# 03_-_28PINS_SCHEMATIC.net
KiCad netlist of a schematic drawn in Altium Designer
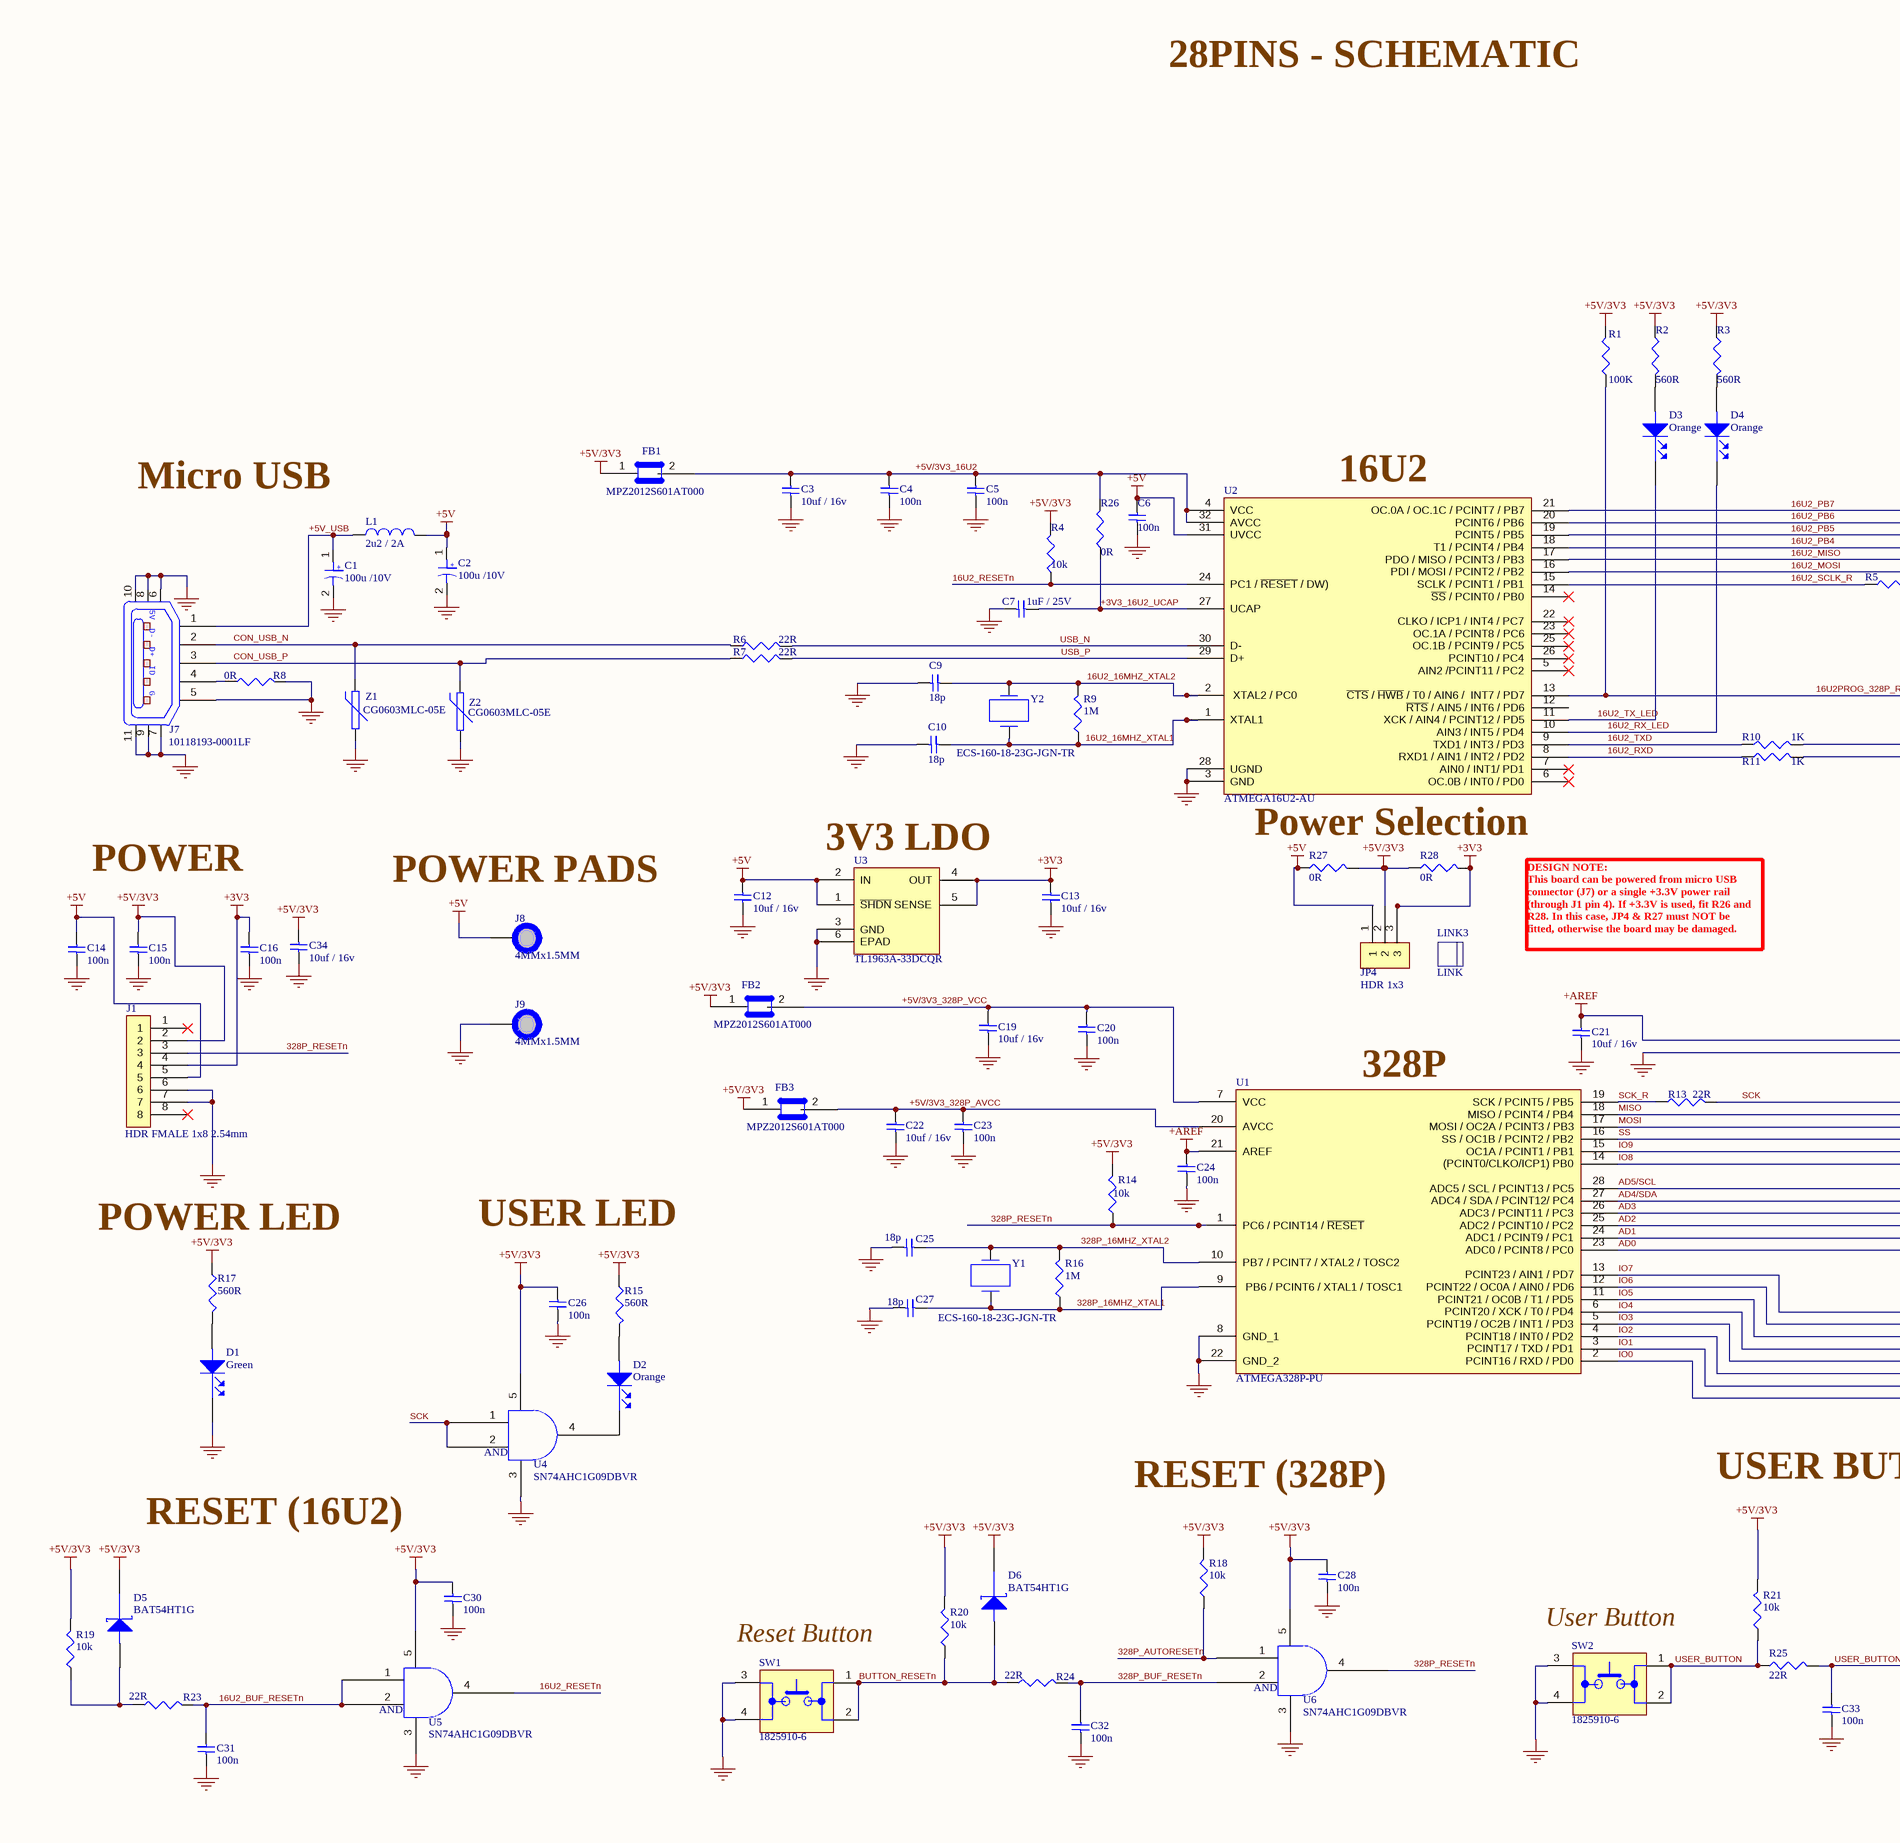
[diagram p0: [03] - 28PINS SCHEMATIC.SchDoc, left]
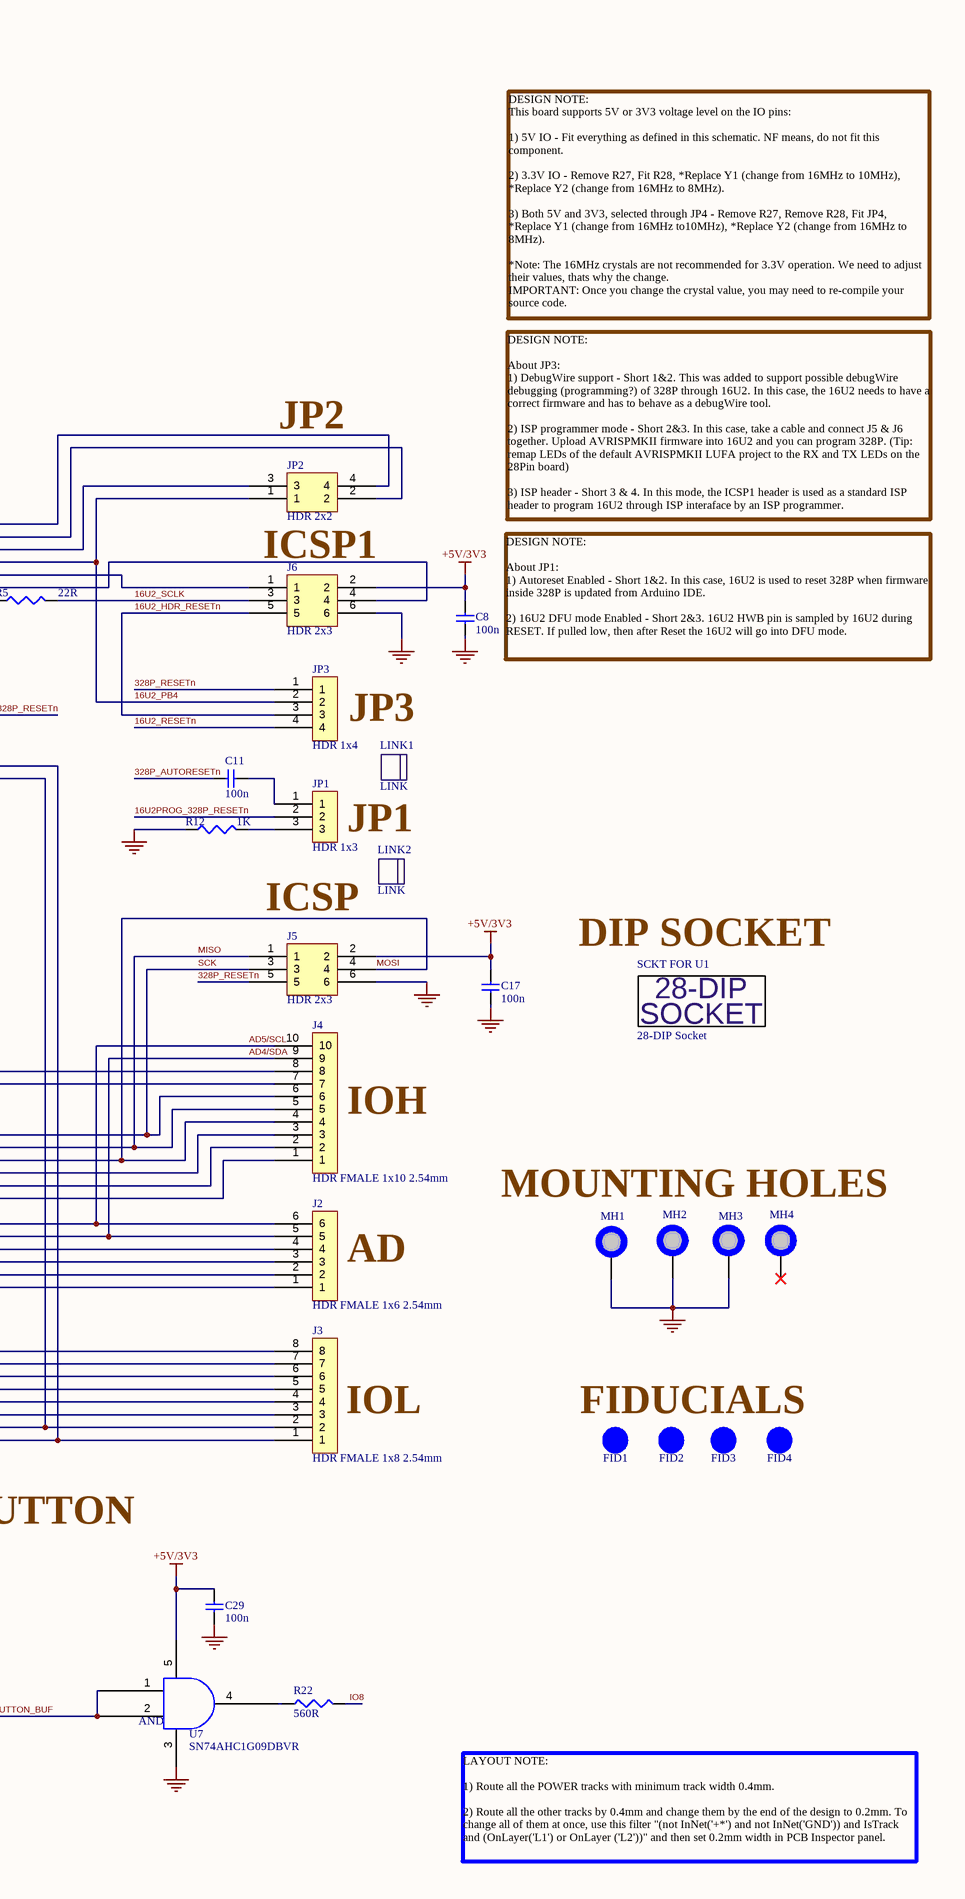
[diagram p1: [03] - 28PINS SCHEMATIC.SchDoc, right]

(export (version "E")
  (design (tool "Eeschema 10.0.6"))
  (components
    (comp (ref "C1")
      (value "100u /10V")
      (footprint "C_ALU_SIZE")
      (fields
        (field (name "MANUFACTURER") "Panasonic")
        (field (name "MANUFACTURER PART NUMBER") "EEE-1AA101WR")
      )
      (libsource (lib "28pins_project") (part "EEE-1AA101WR"))
    )
    (comp (ref "C2")
      (value "100u /10V")
      (footprint "C_ALU_SIZE")
      (fields
        (field (name "MANUFACTURER") "Panasonic")
        (field (name "MANUFACTURER PART NUMBER") "EEE-1AA101WR")
      )
      (libsource (lib "28pins_project") (part "EEE-1AA101WR"))
    )
    (comp (ref "C3")
      (value "10uf / 16v")
      (footprint "C0805")
      (fields
        (field (name "MANUFACTURER") "TDK")
        (field (name "MANUFACTURER PART NUMBER") "C2012X5R1C106M125AC")
      )
      (libsource (lib "28pins_project") (part "C2012X5R1C106M125AC"))
    )
    (comp (ref "C4")
      (value "100n")
      (footprint "C0805")
      (fields
        (field (name "MANUFACTURER") "TDK")
        (field (name "MANUFACTURER PART NUMBER") "C2012X7R1H104K085AA")
      )
      (libsource (lib "28pins_project") (part "C2012X7R1H104K085AA"))
    )
    (comp (ref "C5")
      (value "100n")
      (footprint "C0805")
      (fields
        (field (name "MANUFACTURER") "TDK")
        (field (name "MANUFACTURER PART NUMBER") "C2012X7R1H104K085AA")
      )
      (libsource (lib "28pins_project") (part "C2012X7R1H104K085AA"))
    )
    (comp (ref "C6")
      (value "100n")
      (footprint "C0805")
      (fields
        (field (name "MANUFACTURER") "TDK")
        (field (name "MANUFACTURER PART NUMBER") "C2012X7R1H104K085AA")
      )
      (libsource (lib "28pins_project") (part "C2012X7R1H104K085AA"))
    )
    (comp (ref "C7")
      (value "1uF / 25V")
      (footprint "C0805")
      (fields
        (field (name "MANUFACTURER") "TDK")
        (field (name "MANUFACTURER PART NUMBER") "C2012X5R1E105K125AA")
      )
      (libsource (lib "28pins_project") (part "C2012X5R1E105K125AA"))
    )
    (comp (ref "C8")
      (value "100n")
      (footprint "C0805")
      (fields
        (field (name "MANUFACTURER") "TDK")
        (field (name "MANUFACTURER PART NUMBER") "C2012X7R1H104K085AA")
      )
      (libsource (lib "28pins_project") (part "C2012X7R1H104K085AA"))
    )
    (comp (ref "C9")
      (value "18p")
      (footprint "C0805")
      (fields
        (field (name "MANUFACTURER") "KEMET")
        (field (name "MANUFACTURER PART NUMBER") "C0805C180J5GACTU")
      )
      (libsource (lib "28pins_project") (part "C0805C180J5GACTU"))
    )
    (comp (ref "C10")
      (value "18p")
      (footprint "C0805")
      (fields
        (field (name "MANUFACTURER") "KEMET")
        (field (name "MANUFACTURER PART NUMBER") "C0805C180J5GACTU")
      )
      (libsource (lib "28pins_project") (part "C0805C180J5GACTU"))
    )
    (comp (ref "C11")
      (value "100n")
      (footprint "C0805")
      (fields
        (field (name "MANUFACTURER") "TDK")
        (field (name "MANUFACTURER PART NUMBER") "C2012X7R1H104K085AA")
      )
      (libsource (lib "28pins_project") (part "C2012X7R1H104K085AA"))
    )
    (comp (ref "C12")
      (value "10uf / 16v")
      (footprint "C0805")
      (fields
        (field (name "MANUFACTURER") "TDK")
        (field (name "MANUFACTURER PART NUMBER") "C2012X5R1C106M125AC")
      )
      (libsource (lib "28pins_project") (part "C2012X5R1C106M125AC"))
    )
    (comp (ref "C13")
      (value "10uf / 16v")
      (footprint "C0805")
      (fields
        (field (name "MANUFACTURER") "TDK")
        (field (name "MANUFACTURER PART NUMBER") "C2012X5R1C106M125AC")
      )
      (libsource (lib "28pins_project") (part "C2012X5R1C106M125AC"))
    )
    (comp (ref "C14")
      (value "100n")
      (footprint "C0805")
      (fields
        (field (name "MANUFACTURER") "TDK")
        (field (name "MANUFACTURER PART NUMBER") "C2012X7R1H104K085AA")
      )
      (libsource (lib "28pins_project") (part "C2012X7R1H104K085AA"))
    )
    (comp (ref "C15")
      (value "100n")
      (footprint "C0805")
      (fields
        (field (name "MANUFACTURER") "TDK")
        (field (name "MANUFACTURER PART NUMBER") "C2012X7R1H104K085AA")
      )
      (libsource (lib "28pins_project") (part "C2012X7R1H104K085AA"))
    )
    (comp (ref "C16")
      (value "100n")
      (footprint "C0805")
      (fields
        (field (name "MANUFACTURER") "TDK")
        (field (name "MANUFACTURER PART NUMBER") "C2012X7R1H104K085AA")
      )
      (libsource (lib "28pins_project") (part "C2012X7R1H104K085AA"))
    )
    (comp (ref "C17")
      (value "100n")
      (footprint "C0805")
      (fields
        (field (name "MANUFACTURER") "TDK")
        (field (name "MANUFACTURER PART NUMBER") "C2012X7R1H104K085AA")
      )
      (libsource (lib "28pins_project") (part "C2012X7R1H104K085AA"))
    )
    (comp (ref "C19")
      (value "10uf / 16v")
      (footprint "C0805")
      (fields
        (field (name "MANUFACTURER") "TDK")
        (field (name "MANUFACTURER PART NUMBER") "C2012X5R1C106M125AC")
      )
      (libsource (lib "28pins_project") (part "C2012X5R1C106M125AC"))
    )
    (comp (ref "C20")
      (value "100n")
      (footprint "C0805")
      (fields
        (field (name "MANUFACTURER") "TDK")
        (field (name "MANUFACTURER PART NUMBER") "C2012X7R1H104K085AA")
      )
      (libsource (lib "28pins_project") (part "C2012X7R1H104K085AA"))
    )
    (comp (ref "C21")
      (value "10uf / 16v")
      (footprint "C0805")
      (fields
        (field (name "MANUFACTURER") "TDK")
        (field (name "MANUFACTURER PART NUMBER") "C2012X5R1C106M125AC")
      )
      (libsource (lib "28pins_project") (part "C2012X5R1C106M125AC"))
    )
    (comp (ref "C22")
      (value "10uf / 16v")
      (footprint "C0805")
      (fields
        (field (name "MANUFACTURER") "TDK")
        (field (name "MANUFACTURER PART NUMBER") "C2012X5R1C106M125AC")
      )
      (libsource (lib "28pins_project") (part "C2012X5R1C106M125AC"))
    )
    (comp (ref "C23")
      (value "100n")
      (footprint "C0805")
      (fields
        (field (name "MANUFACTURER") "TDK")
        (field (name "MANUFACTURER PART NUMBER") "C2012X7R1H104K085AA")
      )
      (libsource (lib "28pins_project") (part "C2012X7R1H104K085AA"))
    )
    (comp (ref "C24")
      (value "100n")
      (footprint "C0805")
      (fields
        (field (name "MANUFACTURER") "TDK")
        (field (name "MANUFACTURER PART NUMBER") "C2012X7R1H104K085AA")
      )
      (libsource (lib "28pins_project") (part "C2012X7R1H104K085AA"))
    )
    (comp (ref "C25")
      (value "18p")
      (footprint "C0805")
      (fields
        (field (name "MANUFACTURER") "KEMET")
        (field (name "MANUFACTURER PART NUMBER") "C0805C180J5GACTU")
      )
      (libsource (lib "28pins_project") (part "C0805C180J5GACTU"))
    )
    (comp (ref "C26")
      (value "100n")
      (footprint "C0805")
      (fields
        (field (name "MANUFACTURER") "TDK")
        (field (name "MANUFACTURER PART NUMBER") "C2012X7R1H104K085AA")
      )
      (libsource (lib "28pins_project") (part "C2012X7R1H104K085AA"))
    )
    (comp (ref "C27")
      (value "18p")
      (footprint "C0805")
      (fields
        (field (name "MANUFACTURER") "KEMET")
        (field (name "MANUFACTURER PART NUMBER") "C0805C180J5GACTU")
      )
      (libsource (lib "28pins_project") (part "C0805C180J5GACTU"))
    )
    (comp (ref "C28")
      (value "100n")
      (footprint "C0805")
      (fields
        (field (name "MANUFACTURER") "TDK")
        (field (name "MANUFACTURER PART NUMBER") "C2012X7R1H104K085AA")
      )
      (libsource (lib "28pins_project") (part "C2012X7R1H104K085AA"))
    )
    (comp (ref "C29")
      (value "100n")
      (footprint "C0805")
      (fields
        (field (name "MANUFACTURER") "TDK")
        (field (name "MANUFACTURER PART NUMBER") "C2012X7R1H104K085AA")
      )
      (libsource (lib "28pins_project") (part "C2012X7R1H104K085AA"))
    )
    (comp (ref "C30")
      (value "100n")
      (footprint "C0805")
      (fields
        (field (name "MANUFACTURER") "TDK")
        (field (name "MANUFACTURER PART NUMBER") "C2012X7R1H104K085AA")
      )
      (libsource (lib "28pins_project") (part "C2012X7R1H104K085AA"))
    )
    (comp (ref "C31")
      (value "100n")
      (footprint "C0805")
      (fields
        (field (name "MANUFACTURER") "TDK")
        (field (name "MANUFACTURER PART NUMBER") "C2012X7R1H104K085AA")
      )
      (libsource (lib "28pins_project") (part "C2012X7R1H104K085AA"))
    )
    (comp (ref "C32")
      (value "100n")
      (footprint "C0805")
      (fields
        (field (name "MANUFACTURER") "TDK")
        (field (name "MANUFACTURER PART NUMBER") "C2012X7R1H104K085AA")
      )
      (libsource (lib "28pins_project") (part "C2012X7R1H104K085AA"))
    )
    (comp (ref "C33")
      (value "100n")
      (footprint "C0805")
      (fields
        (field (name "MANUFACTURER") "TDK")
        (field (name "MANUFACTURER PART NUMBER") "C2012X7R1H104K085AA")
      )
      (libsource (lib "28pins_project") (part "C2012X7R1H104K085AA"))
    )
    (comp (ref "C34")
      (value "10uf / 16v")
      (footprint "C0805")
      (fields
        (field (name "MANUFACTURER") "TDK")
        (field (name "MANUFACTURER PART NUMBER") "C2012X5R1C106M125AC")
      )
      (libsource (lib "28pins_project") (part "C2012X5R1C106M125AC"))
    )
    (comp (ref "D1")
      (value "Green")
      (footprint "LED_0603")
      (description "Single Color LED, Green, Colorless Diffused, 1.3mm")
      (fields
        (field (name "MANUFACTURER") "Osram Opto")
        (field (name "MANUFACTURER PART NUMBER") "LGL29K-G2J1-24-Z")
      )
      (libsource (lib "28pins_project") (part "LGL29K-G2J1-24-Z"))
    )
    (comp (ref "D2")
      (value "Orange")
      (footprint "LED_0603")
      (description "Single Color LED, Orange, Colorless Diffused, 1.3mm")
      (fields
        (field (name "MANUFACTURER") "Osram Opto")
        (field (name "MANUFACTURER PART NUMBER") "LOL29K-J2L1-24-Z")
      )
      (libsource (lib "28pins_project") (part "LOL29K-J2L1-24-Z"))
    )
    (comp (ref "D3")
      (value "Orange")
      (footprint "LED_0603")
      (description "Single Color LED, Orange, Colorless Diffused, 1.3mm")
      (fields
        (field (name "MANUFACTURER") "Osram Opto")
        (field (name "MANUFACTURER PART NUMBER") "LOL29K-J2L1-24-Z")
      )
      (libsource (lib "28pins_project") (part "LOL29K-J2L1-24-Z"))
    )
    (comp (ref "D4")
      (value "Orange")
      (footprint "LED_0603")
      (description "Single Color LED, Orange, Colorless Diffused, 1.3mm")
      (fields
        (field (name "MANUFACTURER") "Osram Opto")
        (field (name "MANUFACTURER PART NUMBER") "LOL29K-J2L1-24-Z")
      )
      (libsource (lib "28pins_project") (part "LOL29K-J2L1-24-Z"))
    )
    (comp (ref "D5")
      (value "BAT54HT1G")
      (footprint "SOD323")
      (description "Rectifier Diode, 1 Phase, 1 Element, 0.2A, 30V V(RRM), Silicon")
      (fields (field (name "MANUFACTURER") "ON Semiconductor / Fairchild"))
      (libsource (lib "28pins_project") (part "BAT54HT1G"))
    )
    (comp (ref "D6")
      (value "BAT54HT1G")
      (footprint "SOD323")
      (description "Rectifier Diode, 1 Phase, 1 Element, 0.2A, 30V V(RRM), Silicon")
      (fields (field (name "MANUFACTURER") "ON Semiconductor / Fairchild"))
      (libsource (lib "28pins_project") (part "BAT54HT1G"))
    )
    (comp (ref "FB1")
      (value "MPZ2012S601AT000")
      (footprint "C0805")
      (description "Ferrite Chip, 1 Function(s), 2A")
      (fields (field (name "MANUFACTURER") "TDK"))
      (libsource (lib "28pins_project") (part "MPZ2012S601AT000"))
    )
    (comp (ref "FB2")
      (value "MPZ2012S601AT000")
      (footprint "C0805")
      (description "Ferrite Chip, 1 Function(s), 2A")
      (fields (field (name "MANUFACTURER") "TDK"))
      (libsource (lib "28pins_project") (part "MPZ2012S601AT000"))
    )
    (comp (ref "FB3")
      (value "MPZ2012S601AT000")
      (footprint "C0805")
      (description "Ferrite Chip, 1 Function(s), 2A")
      (fields (field (name "MANUFACTURER") "TDK"))
      (libsource (lib "28pins_project") (part "MPZ2012S601AT000"))
    )
    (comp (ref "FID1")
      (value "FID_1MMC")
      (footprint "FID_40x120D")
      (description "Fiducial 40mil Diameter, 120mil Mask")
      (libsource (lib "28pins_project") (part "FID_1MMC"))
    )
    (comp (ref "FID2")
      (value "FID_1MMC")
      (footprint "FID_40x120D")
      (description "Fiducial 40mil Diameter, 120mil Mask")
      (libsource (lib "28pins_project") (part "FID_1MMC"))
    )
    (comp (ref "FID3")
      (value "FID_1MMC")
      (footprint "FID_40x120D")
      (description "Fiducial 40mil Diameter, 120mil Mask")
      (libsource (lib "28pins_project") (part "FID_1MMC"))
    )
    (comp (ref "FID4")
      (value "FID_1MMC")
      (footprint "FID_40x120D")
      (description "Fiducial 40mil Diameter, 120mil Mask")
      (libsource (lib "28pins_project") (part "FID_1MMC"))
    )
    (comp (ref "J1")
      (value "HDR FMALE 1x8 2.54mm")
      (footprint "Hdr_Female_1x8_2.54mm")
      (fields (field (name "MANUFACTURER") "Harwin") (field (name "MANUFACTURER PART NUMBER") "M20-7820842"))
      (libsource (lib "") (part "M20-7820842_1"))
    )
    (comp (ref "J2")
      (value "HDR FMALE 1x6 2.54mm")
      (footprint "Hdr_Female_1x6_2.5mm")
      (fields (field (name "MANUFACTURER") "Harwin") (field (name "MANUFACTURER PART NUMBER") "M20-7820646"))
      (libsource (lib "28pins_project") (part "M20-7820646"))
    )
    (comp (ref "J3")
      (value "HDR FMALE 1x8 2.54mm")
      (footprint "Hdr_Female_1x8_2.54mm")
      (fields (field (name "MANUFACTURER") "Harwin") (field (name "MANUFACTURER PART NUMBER") "M20-7820842"))
      (libsource (lib "28pins_project") (part "M20-7820842"))
    )
    (comp (ref "J4")
      (value "HDR FMALE 1x10 2.54mm")
      (footprint "Hdr_Female_1x10_2.54mm")
      (fields (field (name "MANUFACTURER") "Harwin") (field (name "MANUFACTURER PART NUMBER") "M20-7821046"))
      (libsource (lib "28pins_project") (part "M20-7821046"))
    )
    (comp (ref "J5")
      (value "HDR 2x3")
      (footprint "HDR_2x3_2.54mm")
      (description "Conn Unshrouded Header HDR 6 POS 2.54mm Solder ST Top Entry Thru-Hole BergStik® Bulk")
      (fields (field (name "MANUFACTURER") "ICC") (field (name "MANUFACTURER PART NUMBER") "67997-106HLF"))
      (libsource (lib "28pins_project") (part "67997-106HLF"))
    )
    (comp (ref "J6")
      (value "HDR 2x3")
      (footprint "HDR_2x3_2.54mm")
      (description "Conn Unshrouded Header HDR 6 POS 2.54mm Solder ST Top Entry Thru-Hole BergStik® Bulk")
      (fields (field (name "MANUFACTURER") "ICC") (field (name "MANUFACTURER PART NUMBER") "67997-106HLF"))
      (libsource (lib "28pins_project") (part "67997-106HLF"))
    )
    (comp (ref "J7")
      (value "10118193-0001LF")
      (footprint "10118193")
      (description "USB Connector, 5 Contact(s), Female, Right Angle, Surface Mount Terminal, Locking, Receptacle")
      (fields (field (name "MANUFACTURER") "Amphenol Communications Solutions"))
      (libsource (lib "28pins_project") (part "10118193-0001LF"))
    )
    (comp (ref "J8")
      (value "4MMx1.5MM")
      (footprint "PAD_WITH_HOLE_4MMx1.5MM")
      (description "PAD_WITH_HOLE_4MMx1.5MM")
      (libsource (lib "28pins_project") (part "PAD_WITH_HOLE_4MMx1.5MM"))
    )
    (comp (ref "J9")
      (value "4MMx1.5MM")
      (footprint "PAD_WITH_HOLE_4MMx1.5MM")
      (description "PAD_WITH_HOLE_4MMx1.5MM")
      (libsource (lib "28pins_project") (part "PAD_WITH_HOLE_4MMx1.5MM"))
    )
    (comp (ref "JP1")
      (value "HDR 1x3")
      (footprint "Hdr_Female_1x3_2.54mm")
      (description "Conn Unshrouded Header HDR 3 POS 2.54mm Solder ST Top Entry Thru-Hole BergStik® Automotive Bulk")
      (fields (field (name "MANUFACTURER") "ICC") (field (name "MANUFACTURER PART NUMBER") "68000-103HLF"))
      (libsource (lib "28pins_project") (part "68000-103HLF"))
    )
    (comp (ref "JP2")
      (value "HDR 2x2")
      (footprint "HDR_2x2_2.54mm")
      (description "Conn Unshrouded Header HDR 4 POS 2.54mm Solder ST Top Entry Thru-Hole BergStik® Bulk")
      (fields
        (field (name "MANUFACTURER") "Amphenol ICC / FCI")
        (field (name "MANUFACTURER PART NUMBER") "68602-204HLF")
      )
      (libsource (lib "28pins_project") (part "68602-204HLF"))
    )
    (comp (ref "JP3")
      (value "HDR 1x4")
      (footprint "Hdr_Female_1x4_2.5mm")
      (description "Conn Unshrouded Header HDR 4 POS 2.54mm Solder ST Thru-Hole Bag")
      (fields
        (field (name "MANUFACTURER") "Amphenol ICC / FCI")
        (field (name "MANUFACTURER PART NUMBER") "68001-204HLF")
      )
      (libsource (lib "28pins_project") (part "68001-204HLF"))
    )
    (comp (ref "JP4")
      (value "HDR 1x3")
      (footprint "Hdr_Female_1x3_2.54mm")
      (description "Conn Unshrouded Header HDR 3 POS 2.54mm Solder ST Top Entry Thru-Hole BergStik® Automotive Bulk")
      (fields (field (name "MANUFACTURER") "ICC") (field (name "MANUFACTURER PART NUMBER") "68000-103HLF"))
      (libsource (lib "") (part "68000-103HLF_1"))
    )
    (comp (ref "L1")
      (value "2u2 / 2A")
      (footprint "C1210_IND")
      (description "General Purpose Inductor, 2.2uH, 20%, 1 Element, Ferrite-Core, SMD, 1210")
      (fields
        (field (name "MANUFACTURER") "KEMET")
        (field (name "MANUFACTURER PART NUMBER") "L1210R2R2MDWIT")
      )
      (libsource (lib "28pins_project") (part "L1210R2R2MDWIT"))
    )
    (comp (ref "LINK1")
      (value "LINK")
      (description "Shunts/Jumper Connector")
      (fields
        (field (name "MANUFACTURER") "Sullins")
        (field (name "MANUFACTURER PART NUMBER") "QPC02SXGN-RC")
      )
      (libsource (lib "28pins_project") (part "QPC02SXGN-RC"))
    )
    (comp (ref "LINK2")
      (value "LINK")
      (description "Shunts/Jumper Connector")
      (fields
        (field (name "MANUFACTURER") "Sullins")
        (field (name "MANUFACTURER PART NUMBER") "QPC02SXGN-RC")
      )
      (libsource (lib "28pins_project") (part "QPC02SXGN-RC"))
    )
    (comp (ref "LINK3")
      (value "LINK")
      (description "Shunts/Jumper Connector")
      (fields
        (field (name "MANUFACTURER") "Sullins")
        (field (name "MANUFACTURER PART NUMBER") "QPC02SXGN-RC")
      )
      (libsource (lib "28pins_project") (part "QPC02SXGN-RC"))
    )
    (comp (ref "MH1")
      (value "MH_7.4MMC_3.2MMD")
      (footprint "MH_7.4MMC_3.2MMD")
      (description "Mounting Hole 7.4mm Diameter, 3.2mm Drill")
      (libsource (lib "28pins_project") (part "MH_7.4MMC_3.2MMD"))
    )
    (comp (ref "MH2")
      (value "MH_7.4MMC_3.2MMD")
      (footprint "MH_7.4MMC_3.2MMD")
      (description "Mounting Hole 7.4mm Diameter, 3.2mm Drill")
      (libsource (lib "28pins_project") (part "MH_7.4MMC_3.2MMD"))
    )
    (comp (ref "MH3")
      (value "MH_7.4MMC_3.2MMD")
      (footprint "MH_7.4MMC_3.2MMD")
      (description "Mounting Hole 7.4mm Diameter, 3.2mm Drill")
      (libsource (lib "28pins_project") (part "MH_7.4MMC_3.2MMD"))
    )
    (comp (ref "MH4")
      (value "MH_7.4MMNC_3.2MMD")
      (footprint "MH_7.4MMC_3.2MMD_NON_COPPER_NPTH")
      (description "Hole 7.4MM Diameter (Non Copper), 3.2MM Drill NPTH")
      (libsource (lib "28pins_project") (part "MH_7.4MMNC_3.2MMD"))
    )
    (comp (ref "R1")
      (value "100K")
      (footprint "R0805")
      (fields
        (field (name "MANUFACTURER") "Yageo")
        (field (name "MANUFACTURER PART NUMBER") "RC0805FR-0710KL")
        (field (name "TOLERANCE") "1%")
      )
      (libsource (lib "28pins_project") (part "RC0805FR-0710KL (3)"))
    )
    (comp (ref "R2")
      (value "560R")
      (footprint "R0805")
      (fields
        (field (name "MANUFACTURER") "Yageo")
        (field (name "MANUFACTURER PART NUMBER") "RC0805FR-075R6L")
        (field (name "TOLERANCE") "1%")
      )
      (libsource (lib "28pins_project") (part "RC0805FR-075R6L"))
    )
    (comp (ref "R3")
      (value "560R")
      (footprint "R0805")
      (fields
        (field (name "MANUFACTURER") "Yageo")
        (field (name "MANUFACTURER PART NUMBER") "RC0805FR-075R6L")
        (field (name "TOLERANCE") "1%")
      )
      (libsource (lib "28pins_project") (part "RC0805FR-075R6L"))
    )
    (comp (ref "R4")
      (value "10k")
      (footprint "R0805")
      (fields
        (field (name "MANUFACTURER") "Yageo")
        (field (name "MANUFACTURER PART NUMBER") "RC0805FR-0710KL")
        (field (name "TOLERANCE") "1%")
      )
      (libsource (lib "28pins_project") (part "RC0805FR-0710KL (2)"))
    )
    (comp (ref "R5")
      (value "22R")
      (footprint "R0805")
      (fields
        (field (name "MANUFACTURER") "Yageo")
        (field (name "MANUFACTURER PART NUMBER") "RC0805FR-0722RL")
        (field (name "TOLERANCE") "1%")
      )
      (libsource (lib "28pins_project") (part "RC0805FR-0722RL"))
    )
    (comp (ref "R6")
      (value "22R")
      (footprint "R0805")
      (fields
        (field (name "MANUFACTURER") "Yageo")
        (field (name "MANUFACTURER PART NUMBER") "RC0805FR-0722RL")
        (field (name "TOLERANCE") "1%")
      )
      (libsource (lib "28pins_project") (part "RC0805FR-0722RL"))
    )
    (comp (ref "R7")
      (value "22R")
      (footprint "R0805")
      (fields
        (field (name "MANUFACTURER") "Yageo")
        (field (name "MANUFACTURER PART NUMBER") "RC0805FR-0722RL")
        (field (name "TOLERANCE") "1%")
      )
      (libsource (lib "28pins_project") (part "RC0805FR-0722RL"))
    )
    (comp (ref "R8")
      (value "0R")
      (footprint "R0805")
      (description "Metal Glaze/thick Film, 0.125W, 0ohm, Surface Mount, 0805")
      (fields
        (field (name "MANUFACTURER") "Yageo")
        (field (name "MANUFACTURER PART NUMBER") "RC0805JR-070RL")
      )
      (libsource (lib "28pins_project") (part "RC0805JR-070RL"))
    )
    (comp (ref "R9")
      (value "1M")
      (footprint "R0805")
      (fields
        (field (name "MANUFACTURER") "Yageo")
        (field (name "MANUFACTURER PART NUMBER") "RC0805FR-071ML")
        (field (name "TOLERANCE") "1%")
      )
      (libsource (lib "28pins_project") (part "RC0805FR-071ML"))
    )
    (comp (ref "R10")
      (value "1K")
      (footprint "R0805")
      (fields
        (field (name "MANUFACTURER") "Yageo")
        (field (name "MANUFACTURER PART NUMBER") "RC0805FR-0710KL")
        (field (name "TOLERANCE") "1%")
      )
      (libsource (lib "28pins_project") (part "RC0805FR-0710KL"))
    )
    (comp (ref "R11")
      (value "1K")
      (footprint "R0805")
      (fields
        (field (name "MANUFACTURER") "Yageo")
        (field (name "MANUFACTURER PART NUMBER") "RC0805FR-0710KL")
        (field (name "TOLERANCE") "1%")
      )
      (libsource (lib "28pins_project") (part "RC0805FR-0710KL"))
    )
    (comp (ref "R12")
      (value "1K")
      (footprint "R0805")
      (fields
        (field (name "MANUFACTURER") "Yageo")
        (field (name "MANUFACTURER PART NUMBER") "RC0805FR-0710KL")
        (field (name "TOLERANCE") "1%")
      )
      (libsource (lib "28pins_project") (part "RC0805FR-0710KL"))
    )
    (comp (ref "R13")
      (value "22R")
      (footprint "R0805")
      (fields
        (field (name "MANUFACTURER") "Yageo")
        (field (name "MANUFACTURER PART NUMBER") "RC0805FR-0722RL")
        (field (name "TOLERANCE") "1%")
      )
      (libsource (lib "28pins_project") (part "RC0805FR-0722RL"))
    )
    (comp (ref "R14")
      (value "10k")
      (footprint "R0805")
      (fields
        (field (name "MANUFACTURER") "Yageo")
        (field (name "MANUFACTURER PART NUMBER") "RC0805FR-0710KL")
        (field (name "TOLERANCE") "1%")
      )
      (libsource (lib "28pins_project") (part "RC0805FR-0710KL (2)"))
    )
    (comp (ref "R15")
      (value "560R")
      (footprint "R0805")
      (fields
        (field (name "MANUFACTURER") "Yageo")
        (field (name "MANUFACTURER PART NUMBER") "RC0805FR-075R6L")
        (field (name "TOLERANCE") "1%")
      )
      (libsource (lib "28pins_project") (part "RC0805FR-075R6L"))
    )
    (comp (ref "R16")
      (value "1M")
      (footprint "R0805")
      (fields
        (field (name "MANUFACTURER") "Yageo")
        (field (name "MANUFACTURER PART NUMBER") "RC0805FR-071ML")
        (field (name "TOLERANCE") "1%")
      )
      (libsource (lib "28pins_project") (part "RC0805FR-071ML"))
    )
    (comp (ref "R17")
      (value "560R")
      (footprint "R0805")
      (fields
        (field (name "MANUFACTURER") "Yageo")
        (field (name "MANUFACTURER PART NUMBER") "RC0805FR-075R6L")
        (field (name "TOLERANCE") "1%")
      )
      (libsource (lib "28pins_project") (part "RC0805FR-075R6L"))
    )
    (comp (ref "R18")
      (value "10k")
      (footprint "R0805")
      (fields
        (field (name "MANUFACTURER") "Yageo")
        (field (name "MANUFACTURER PART NUMBER") "RC0805FR-0710KL")
        (field (name "TOLERANCE") "1%")
      )
      (libsource (lib "28pins_project") (part "RC0805FR-0710KL (2)"))
    )
    (comp (ref "R19")
      (value "10k")
      (footprint "R0805")
      (fields
        (field (name "MANUFACTURER") "Yageo")
        (field (name "MANUFACTURER PART NUMBER") "RC0805FR-0710KL")
        (field (name "TOLERANCE") "1%")
      )
      (libsource (lib "28pins_project") (part "RC0805FR-0710KL (2)"))
    )
    (comp (ref "R20")
      (value "10k")
      (footprint "R0805")
      (fields
        (field (name "MANUFACTURER") "Yageo")
        (field (name "MANUFACTURER PART NUMBER") "RC0805FR-0710KL")
        (field (name "TOLERANCE") "1%")
      )
      (libsource (lib "28pins_project") (part "RC0805FR-0710KL (2)"))
    )
    (comp (ref "R21")
      (value "10k")
      (footprint "R0805")
      (fields
        (field (name "MANUFACTURER") "Yageo")
        (field (name "MANUFACTURER PART NUMBER") "RC0805FR-0710KL")
        (field (name "TOLERANCE") "1%")
      )
      (libsource (lib "28pins_project") (part "RC0805FR-0710KL (2)"))
    )
    (comp (ref "R22")
      (value "560R")
      (footprint "R0805")
      (fields
        (field (name "MANUFACTURER") "Yageo")
        (field (name "MANUFACTURER PART NUMBER") "RC0805FR-075R6L")
        (field (name "TOLERANCE") "1%")
      )
      (libsource (lib "28pins_project") (part "RC0805FR-075R6L"))
    )
    (comp (ref "R23")
      (value "22R")
      (footprint "R0805")
      (fields
        (field (name "MANUFACTURER") "Yageo")
        (field (name "MANUFACTURER PART NUMBER") "RC0805FR-0722RL")
        (field (name "TOLERANCE") "1%")
      )
      (libsource (lib "28pins_project") (part "RC0805FR-0722RL"))
    )
    (comp (ref "R24")
      (value "22R")
      (footprint "R0805")
      (fields
        (field (name "MANUFACTURER") "Yageo")
        (field (name "MANUFACTURER PART NUMBER") "RC0805FR-0722RL")
        (field (name "TOLERANCE") "1%")
      )
      (libsource (lib "28pins_project") (part "RC0805FR-0722RL"))
    )
    (comp (ref "R25")
      (value "22R")
      (footprint "R0805")
      (fields
        (field (name "MANUFACTURER") "Yageo")
        (field (name "MANUFACTURER PART NUMBER") "RC0805FR-0722RL")
        (field (name "TOLERANCE") "1%")
      )
      (libsource (lib "28pins_project") (part "RC0805FR-0722RL"))
    )
    (comp (ref "R26")
      (value "0R")
      (footprint "R0805")
      (description "Metal Glaze/thick Film, 0.125W, 0ohm, Surface Mount, 0805")
      (fields
        (field (name "MANUFACTURER") "Yageo")
        (field (name "MANUFACTURER PART NUMBER") "RC0805JR-070RL")
      )
      (libsource (lib "28pins_project") (part "RC0805JR-070RL"))
    )
    (comp (ref "R27")
      (value "0R")
      (footprint "R0805")
      (description "Metal Glaze/thick Film, 0.125W, 0ohm, Surface Mount, 0805")
      (fields
        (field (name "MANUFACTURER") "Yageo")
        (field (name "MANUFACTURER PART NUMBER") "RC0805JR-070RL")
      )
      (libsource (lib "28pins_project") (part "RC0805JR-070RL"))
    )
    (comp (ref "R28")
      (value "0R")
      (footprint "R0805")
      (description "Metal Glaze/thick Film, 0.125W, 0ohm, Surface Mount, 0805")
      (fields
        (field (name "MANUFACTURER") "Yageo")
        (field (name "MANUFACTURER PART NUMBER") "RC0805JR-070RL")
      )
      (libsource (lib "28pins_project") (part "RC0805JR-070RL"))
    )
    (comp (ref "SCKT FOR U1")
      (value "28-DIP Socket")
      (footprint "28_DIP_7.62MM_SOCKET")
      (description "IC Socket, DIP28, 28 Contact(s)")
      (fields (field (name "MANUFACTURER") "3M") (field (name "MANUFACTURER PART NUMBER") "4828-3004-CP"))
      (libsource (lib "28pins_project") (part "4828-3004-CP"))
    )
    (comp (ref "SW1")
      (value "1825910-6")
      (footprint "1825910-6")
      (fields (field (name "MANUFACTURER") "TE Connectivity Alcoswitch"))
      (libsource (lib "28pins_project") (part "1825910-6"))
    )
    (comp (ref "SW2")
      (value "1825910-6")
      (footprint "1825910-6")
      (fields (field (name "MANUFACTURER") "TE Connectivity Alcoswitch"))
      (libsource (lib "28pins_project") (part "1825910-6"))
    )
    (comp (ref "U1")
      (value "ATMEGA328P-PU")
      (footprint "28_DIP_7.62mm")
      (description "RISC Microcontroller, 8-Bit, FLASH, AVR RISC CPU, 20MHz, CMOS, PDIP28")
      (fields (field (name "MANUFACTURER") "Microchip"))
      (libsource (lib "28pins_project") (part "ATMEGA328P-PU"))
    )
    (comp (ref "U2")
      (value "ATMEGA16U2-AU")
      (footprint "TQFP32")
      (description "RISC Microcontroller, 8-Bit, FLASH, AVR RISC CPU, 16MHz, CMOS, PQFP32")
      (fields (field (name "MANUFACTURER") "Microchip"))
      (libsource (lib "28pins_project") (part "ATMEGA16U2-AU"))
    )
    (comp (ref "U3")
      (value "TL1963A-33DCQR")
      (footprint "DCQ (R-PDSO-G6)")
      (description "Fixed Positive LDO Regulator, 3.3V, 0.55V Dropout, BIPolar, PDSO6")
      (fields (field (name "MANUFACTURER") "Texas Instruments"))
      (libsource (lib "28pins_project") (part "TL1963A-33DCQR"))
    )
    (comp (ref "U4")
      (value "SN74AHC1G09DBVR")
      (footprint "DBV_SOT_23_5")
      (description "AND Gate, AHC/VHC/H/U/V Series, 1-Func, 2-Input, CMOS, PDSO5")
      (fields (field (name "MANUFACTURER") "Texas Instruments"))
      (libsource (lib "28pins_project") (part "SN74AHC1G09DBVR"))
    )
    (comp (ref "U5")
      (value "SN74AHC1G09DBVR")
      (footprint "DBV_SOT_23_5")
      (description "AND Gate, AHC/VHC/H/U/V Series, 1-Func, 2-Input, CMOS, PDSO5")
      (fields (field (name "MANUFACTURER") "Texas Instruments"))
      (libsource (lib "28pins_project") (part "SN74AHC1G09DBVR"))
    )
    (comp (ref "U6")
      (value "SN74AHC1G09DBVR")
      (footprint "DBV_SOT_23_5")
      (description "AND Gate, AHC/VHC/H/U/V Series, 1-Func, 2-Input, CMOS, PDSO5")
      (fields (field (name "MANUFACTURER") "Texas Instruments"))
      (libsource (lib "28pins_project") (part "SN74AHC1G09DBVR"))
    )
    (comp (ref "U7")
      (value "SN74AHC1G09DBVR")
      (footprint "DBV_SOT_23_5")
      (description "AND Gate, AHC/VHC/H/U/V Series, 1-Func, 2-Input, CMOS, PDSO5")
      (fields (field (name "MANUFACTURER") "Texas Instruments"))
      (libsource (lib "28pins_project") (part "SN74AHC1G09DBVR"))
    )
    (comp (ref "Y1")
      (value "ECS-160-18-23G-JGN-TR")
      (footprint "ECS-160-18_BIG")
      (description "Parallel - Fundamental Quartz Crystal, 16MHz Nom")
      (fields (field (name "MANUFACTURER") "ECS International"))
      (libsource (lib "28pins_project") (part "ECS-160-18-23G-JGN-TR"))
    )
    (comp (ref "Y2")
      (value "ECS-160-18-23G-JGN-TR")
      (footprint "ECS-160-18_BIG")
      (description "Parallel - Fundamental Quartz Crystal, 16MHz Nom")
      (fields (field (name "MANUFACTURER") "ECS International"))
      (libsource (lib "28pins_project") (part "ECS-160-18-23G-JGN-TR"))
    )
    (comp (ref "Z1")
      (value "CG0603MLC-05E")
      (footprint "R0603")
      (description "Varistor, 5V, Surface Mount")
      (fields (field (name "MANUFACTURER") "Bourns"))
      (libsource (lib "28pins_project") (part "CG0603MLC-05E"))
    )
    (comp (ref "Z2")
      (value "CG0603MLC-05E")
      (footprint "R0603")
      (description "Varistor, 5V, Surface Mount")
      (fields (field (name "MANUFACTURER") "Bourns"))
      (libsource (lib "28pins_project") (part "CG0603MLC-05E"))
    )
  )
  (nets
    (net (code "1") (name "+3V3") (class "Default")
      (node (ref "C13") (pin "1") (pinfunction "1_1") (pintype "passive"))
      (node (ref "C16") (pin "2") (pinfunction "2_2") (pintype "passive"))
      (node (ref "J1") (pin "4") (pinfunction "4_4") (pintype "passive"))
      (node (ref "JP4") (pin "3") (pinfunction "3_3") (pintype "passive"))
      (node (ref "R28") (pin "2") (pinfunction "4_2") (pintype "passive"))
      (node (ref "U3") (pin "4") (pinfunction "OUT_4") (pintype "passive"))
      (node (ref "U3") (pin "5") (pinfunction "SENSE_5") (pintype "passive"))
    )
    (net (code "2") (name "+5V") (class "Default")
      (node (ref "C12") (pin "1") (pinfunction "1_1") (pintype "passive"))
      (node (ref "C14") (pin "2") (pinfunction "2_2") (pintype "passive"))
      (node (ref "C2") (pin "1") (pinfunction "1_1") (pintype "passive"))
      (node (ref "C6") (pin "2") (pinfunction "2_2") (pintype "passive"))
      (node (ref "J1") (pin "5") (pinfunction "5_5") (pintype "passive"))
      (node (ref "J8") (pin "1") (pinfunction "1_1") (pintype "passive"))
      (node (ref "JP4") (pin "1") (pinfunction "1_1") (pintype "passive"))
      (node (ref "L1") (pin "2") (pinfunction "2_2") (pintype "passive"))
      (node (ref "R27") (pin "1") (pinfunction "3_1") (pintype "passive"))
      (node (ref "U2") (pin "31") (pinfunction "UVCC_31") (pintype "passive"))
      (node (ref "U3") (pin "1") (pinfunction "~{SHDN}_1") (pintype "passive"))
      (node (ref "U3") (pin "2") (pinfunction "IN_2") (pintype "passive"))
    )
    (net (code "3") (name "+5V{slash}3V3") (class "Default")
      (node (ref "C15") (pin "2") (pinfunction "2_2") (pintype "passive"))
      (node (ref "C17") (pin "2") (pinfunction "2_2") (pintype "passive"))
      (node (ref "C26") (pin "1") (pinfunction "1_1") (pintype "passive"))
      (node (ref "C28") (pin "2") (pinfunction "2_2") (pintype "passive"))
      (node (ref "C29") (pin "2") (pinfunction "2_2") (pintype "passive"))
      (node (ref "C30") (pin "2") (pinfunction "2_2") (pintype "passive"))
      (node (ref "C34") (pin "2") (pinfunction "2_2") (pintype "passive"))
      (node (ref "C8") (pin "2") (pinfunction "2_2") (pintype "passive"))
      (node (ref "D5") (pin "1") (pinfunction "Cathode_1") (pintype "passive"))
      (node (ref "D6") (pin "1") (pinfunction "Cathode_1") (pintype "passive"))
      (node (ref "FB1") (pin "1") (pinfunction "1_1") (pintype "passive"))
      (node (ref "FB2") (pin "1") (pinfunction "1_1") (pintype "passive"))
      (node (ref "FB3") (pin "1") (pinfunction "1_1") (pintype "passive"))
      (node (ref "J1") (pin "2") (pinfunction "2_2") (pintype "passive"))
      (node (ref "J5") (pin "2") (pinfunction "2_2") (pintype "passive"))
      (node (ref "J6") (pin "2") (pinfunction "2_2") (pintype "passive"))
      (node (ref "JP4") (pin "2") (pinfunction "2_2") (pintype "passive"))
      (node (ref "R1") (pin "2") (pinfunction "4_2") (pintype "passive"))
      (node (ref "R14") (pin "2") (pinfunction "4_2") (pintype "passive"))
      (node (ref "R15") (pin "1") (pinfunction "3_1") (pintype "passive"))
      (node (ref "R17") (pin "1") (pinfunction "3_1") (pintype "passive"))
      (node (ref "R18") (pin "2") (pinfunction "4_2") (pintype "passive"))
      (node (ref "R19") (pin "2") (pinfunction "4_2") (pintype "passive"))
      (node (ref "R2") (pin "1") (pinfunction "3_1") (pintype "passive"))
      (node (ref "R20") (pin "2") (pinfunction "4_2") (pintype "passive"))
      (node (ref "R21") (pin "2") (pinfunction "4_2") (pintype "passive"))
      (node (ref "R27") (pin "2") (pinfunction "4_2") (pintype "passive"))
      (node (ref "R28") (pin "1") (pinfunction "3_1") (pintype "passive"))
      (node (ref "R3") (pin "1") (pinfunction "3_1") (pintype "passive"))
      (node (ref "R4") (pin "2") (pinfunction "4_2") (pintype "passive"))
      (node (ref "U4") (pin "5") (pinfunction "5_5") (pintype "passive"))
      (node (ref "U5") (pin "5") (pinfunction "5_5") (pintype "passive"))
      (node (ref "U6") (pin "5") (pinfunction "5_5") (pintype "passive"))
      (node (ref "U7") (pin "5") (pinfunction "5_5") (pintype "passive"))
    )
    (net (code "4") (name "+AREF") (class "Default")
      (node (ref "C21") (pin "2") (pinfunction "2_2") (pintype "passive"))
      (node (ref "C24") (pin "2") (pinfunction "2_2") (pintype "passive"))
      (node (ref "J4") (pin "8") (pinfunction "8_8") (pintype "passive"))
      (node (ref "U1") (pin "21") (pinfunction "AREF_21") (pintype "passive"))
    )
    (net (code "5") (name "/+3V3_16U2_UCAP") (class "Default")
      (node (ref "C7") (pin "2") (pinfunction "2_2") (pintype "passive"))
      (node (ref "R26") (pin "1") (pinfunction "3_1") (pintype "passive"))
      (node (ref "U2") (pin "27") (pinfunction "UCAP_27") (pintype "passive"))
    )
    (net (code "6") (name "/+5V_USB") (class "Default")
      (node (ref "C1") (pin "1") (pinfunction "1_1") (pintype "passive"))
      (node (ref "J7") (pin "1") (pinfunction "1_1") (pintype "passive"))
      (node (ref "L1") (pin "1") (pinfunction "1_1") (pintype "passive"))
    )
    (net (code "7") (name "/+5V{slash}3V3_16U2") (class "Default")
      (node (ref "C3") (pin "2") (pinfunction "2_2") (pintype "passive"))
      (node (ref "C4") (pin "2") (pinfunction "2_2") (pintype "passive"))
      (node (ref "C5") (pin "2") (pinfunction "2_2") (pintype "passive"))
      (node (ref "FB1") (pin "2") (pinfunction "2_2") (pintype "passive"))
      (node (ref "R26") (pin "2") (pinfunction "4_2") (pintype "passive"))
      (node (ref "U2") (pin "32") (pinfunction "AVCC_32") (pintype "passive"))
      (node (ref "U2") (pin "4") (pinfunction "VCC_4") (pintype "passive"))
    )
    (net (code "8") (name "/+5V{slash}3V3_328P_AVCC") (class "Default")
      (node (ref "C22") (pin "2") (pinfunction "2_2") (pintype "passive"))
      (node (ref "C23") (pin "2") (pinfunction "2_2") (pintype "passive"))
      (node (ref "FB3") (pin "2") (pinfunction "2_2") (pintype "passive"))
      (node (ref "U1") (pin "20") (pinfunction "AVCC_20") (pintype "passive"))
    )
    (net (code "9") (name "/+5V{slash}3V3_328P_VCC") (class "Default")
      (node (ref "C19") (pin "2") (pinfunction "2_2") (pintype "passive"))
      (node (ref "C20") (pin "2") (pinfunction "2_2") (pintype "passive"))
      (node (ref "FB2") (pin "2") (pinfunction "2_2") (pintype "passive"))
      (node (ref "U1") (pin "7") (pinfunction "VCC_7") (pintype "passive"))
    )
    (net (code "10") (name "/16U2PROG_328P_RESETn") (class "Default")
      (node (ref "JP1") (pin "2") (pinfunction "2_2") (pintype "passive"))
      (node (ref "R1") (pin "1") (pinfunction "3_1") (pintype "passive"))
      (node (ref "U2") (pin "13") (pinfunction "~{CTS}_/_~{HWB}_/_T0_/_AIN6_/__INT7_/_PD7_13") (pintype "passive"))
    )
    (net (code "11") (name "/16U2_16MHZ_XTAL1") (class "Default")
      (node (ref "C10") (pin "2") (pinfunction "2_2") (pintype "passive"))
      (node (ref "R9") (pin "1") (pinfunction "3_1") (pintype "passive"))
      (node (ref "U2") (pin "1") (pinfunction "XTAL1_1") (pintype "passive"))
      (node (ref "Y2") (pin "1") (pinfunction "1_1") (pintype "passive"))
    )
    (net (code "12") (name "/16U2_16MHZ_XTAL2") (class "Default")
      (node (ref "C9") (pin "2") (pinfunction "2_2") (pintype "passive"))
      (node (ref "R9") (pin "2") (pinfunction "4_2") (pintype "passive"))
      (node (ref "U2") (pin "2") (pinfunction "_XTAL2_/_PC0_2") (pintype "passive"))
      (node (ref "Y2") (pin "2") (pinfunction "2_2") (pintype "passive"))
    )
    (net (code "13") (name "/16U2_BUF_RESETn") (class "Default")
      (node (ref "C31") (pin "2") (pinfunction "2_2") (pintype "passive"))
      (node (ref "R23") (pin "2") (pinfunction "4_2") (pintype "passive"))
      (node (ref "U5") (pin "1") (pinfunction "1_1") (pintype "passive"))
      (node (ref "U5") (pin "2") (pinfunction "2_2") (pintype "passive"))
    )
    (net (code "14") (name "/16U2_HDR_RESETn") (class "Default")
      (node (ref "J6") (pin "5") (pinfunction "5_5") (pintype "passive"))
      (node (ref "JP3") (pin "3") (pinfunction "3_3") (pintype "passive"))
    )
    (net (code "15") (name "/16U2_MISO") (class "Default")
      (node (ref "J6") (pin "1") (pinfunction "1_1") (pintype "passive"))
      (node (ref "U2") (pin "17") (pinfunction "PDO_/_MISO_/_PCINT3_/_PB3_17") (pintype "passive"))
    )
    (net (code "16") (name "/16U2_MOSI") (class "Default")
      (node (ref "J6") (pin "4") (pinfunction "4_4") (pintype "passive"))
      (node (ref "U2") (pin "16") (pinfunction "PDI_/_MOSI_/_PCINT2_/_PB2_16") (pintype "passive"))
    )
    (net (code "17") (name "/16U2_PB4") (class "Default")
      (node (ref "JP2") (pin "1") (pinfunction "1_1") (pintype "passive"))
      (node (ref "JP3") (pin "2") (pinfunction "2_2") (pintype "passive"))
      (node (ref "U2") (pin "18") (pinfunction "T1_/_PCINT4_/_PB4_18") (pintype "passive"))
    )
    (net (code "18") (name "/16U2_PB5") (class "Default")
      (node (ref "JP2") (pin "3") (pinfunction "3_3") (pintype "passive"))
      (node (ref "U2") (pin "19") (pinfunction "PCINT5_/_PB5_19") (pintype "passive"))
    )
    (net (code "19") (name "/16U2_PB6") (class "Default")
      (node (ref "JP2") (pin "2") (pinfunction "2_2") (pintype "passive"))
      (node (ref "U2") (pin "20") (pinfunction "PCINT6_/_PB6_20") (pintype "passive"))
    )
    (net (code "20") (name "/16U2_PB7") (class "Default")
      (node (ref "JP2") (pin "4") (pinfunction "4_4") (pintype "passive"))
      (node (ref "U2") (pin "21") (pinfunction "OC.0A_/_OC.1C_/_PCINT7_/_PB7_21") (pintype "passive"))
    )
    (net (code "21") (name "/16U2_RESETn") (class "Default")
      (node (ref "JP3") (pin "4") (pinfunction "4_4") (pintype "passive"))
      (node (ref "R4") (pin "1") (pinfunction "3_1") (pintype "passive"))
      (node (ref "U2") (pin "24") (pinfunction "PC1_/_~{RESET}_/_DW)_24") (pintype "passive"))
      (node (ref "U5") (pin "4") (pinfunction "4_4") (pintype "passive"))
    )
    (net (code "22") (name "/16U2_RXD") (class "Default")
      (node (ref "R11") (pin "1") (pinfunction "3_1") (pintype "passive"))
      (node (ref "U2") (pin "8") (pinfunction "RXD1_/_AIN1_/_INT2_/_PD2_8") (pintype "passive"))
    )
    (net (code "23") (name "/16U2_RX_LED") (class "Default")
      (node (ref "D4") (pin "1") (pinfunction "Cathode_1") (pintype "passive"))
      (node (ref "U2") (pin "10") (pinfunction "AIN3_/_INT5_/_PD4_10") (pintype "passive"))
    )
    (net (code "24") (name "/16U2_SCLK") (class "Default")
      (node (ref "J6") (pin "3") (pinfunction "3_3") (pintype "passive"))
      (node (ref "R5") (pin "2") (pinfunction "4_2") (pintype "passive"))
    )
    (net (code "25") (name "/16U2_SCLK_R") (class "Default")
      (node (ref "R5") (pin "1") (pinfunction "3_1") (pintype "passive"))
      (node (ref "U2") (pin "15") (pinfunction "SCLK_/_PCINT1_/_PB1_15") (pintype "passive"))
    )
    (net (code "26") (name "/16U2_TXD") (class "Default")
      (node (ref "R10") (pin "1") (pinfunction "3_1") (pintype "passive"))
      (node (ref "U2") (pin "9") (pinfunction "TXD1_/_INT3_/_PD3_9") (pintype "passive"))
    )
    (net (code "27") (name "/16U2_TX_LED") (class "Default")
      (node (ref "D3") (pin "1") (pinfunction "Cathode_1") (pintype "passive"))
      (node (ref "U2") (pin "11") (pinfunction "XCK_/_AIN4_/_PCINT12_/_PD5_11") (pintype "passive"))
    )
    (net (code "28") (name "/328P_16MHZ_XTAL1") (class "Default")
      (node (ref "C27") (pin "2") (pinfunction "2_2") (pintype "passive"))
      (node (ref "R16") (pin "1") (pinfunction "3_1") (pintype "passive"))
      (node (ref "U1") (pin "9") (pinfunction "_PB6_/_PCINT6_/_XTAL1_/_TOSC1_9") (pintype "passive"))
      (node (ref "Y1") (pin "1") (pinfunction "1_1") (pintype "passive"))
    )
    (net (code "29") (name "/328P_16MHZ_XTAL2") (class "Default")
      (node (ref "C25") (pin "2") (pinfunction "2_2") (pintype "passive"))
      (node (ref "R16") (pin "2") (pinfunction "4_2") (pintype "passive"))
      (node (ref "U1") (pin "10") (pinfunction "PB7_/_PCINT7_/_XTAL2_/_TOSC2_10") (pintype "passive"))
      (node (ref "Y1") (pin "2") (pinfunction "2_2") (pintype "passive"))
    )
    (net (code "30") (name "/328P_AUTORESETn") (class "Default")
      (node (ref "C11") (pin "1") (pinfunction "1_1") (pintype "passive"))
      (node (ref "R18") (pin "1") (pinfunction "3_1") (pintype "passive"))
      (node (ref "U6") (pin "1") (pinfunction "1_1") (pintype "passive"))
    )
    (net (code "31") (name "/328P_BUF_RESETn") (class "Default")
      (node (ref "C32") (pin "2") (pinfunction "2_2") (pintype "passive"))
      (node (ref "R24") (pin "2") (pinfunction "4_2") (pintype "passive"))
      (node (ref "U6") (pin "2") (pinfunction "2_2") (pintype "passive"))
    )
    (net (code "32") (name "/328P_RESETn") (class "Default")
      (node (ref "J1") (pin "3") (pinfunction "3_3") (pintype "passive"))
      (node (ref "J5") (pin "5") (pinfunction "5_5") (pintype "passive"))
      (node (ref "JP3") (pin "1") (pinfunction "1_1") (pintype "passive"))
      (node (ref "R14") (pin "1") (pinfunction "3_1") (pintype "passive"))
      (node (ref "U1") (pin "1") (pinfunction "PC6_/_PCINT14_/_~{RESET}_1") (pintype "passive"))
      (node (ref "U6") (pin "4") (pinfunction "4_4") (pintype "passive"))
    )
    (net (code "33") (name "/AD0") (class "Default")
      (node (ref "J2") (pin "1") (pinfunction "1_1") (pintype "passive"))
      (node (ref "U1") (pin "23") (pinfunction "ADC0_/_PCINT8_/_PC0_23") (pintype "passive"))
    )
    (net (code "34") (name "/AD1") (class "Default")
      (node (ref "J2") (pin "2") (pinfunction "2_2") (pintype "passive"))
      (node (ref "U1") (pin "24") (pinfunction "ADC1_/_PCINT9_/_PC1_24") (pintype "passive"))
    )
    (net (code "35") (name "/AD2") (class "Default")
      (node (ref "J2") (pin "3") (pinfunction "3_3") (pintype "passive"))
      (node (ref "U1") (pin "25") (pinfunction "ADC2_/_PCINT10_/_PC2_25") (pintype "passive"))
    )
    (net (code "36") (name "/AD3") (class "Default")
      (node (ref "J2") (pin "4") (pinfunction "4_4") (pintype "passive"))
      (node (ref "U1") (pin "26") (pinfunction "ADC3_/_PCINT11_/_PC3_26") (pintype "passive"))
    )
    (net (code "37") (name "/AD4{slash}SDA") (class "Default")
      (node (ref "J2") (pin "5") (pinfunction "5_5") (pintype "passive"))
      (node (ref "J4") (pin "9") (pinfunction "9_9") (pintype "passive"))
      (node (ref "U1") (pin "27") (pinfunction "ADC4_/_SDA_/_PCINT12/_PC4_27") (pintype "passive"))
    )
    (net (code "38") (name "/AD5{slash}SCL") (class "Default")
      (node (ref "J2") (pin "6") (pinfunction "6_6") (pintype "passive"))
      (node (ref "J4") (pin "10") (pinfunction "10_10") (pintype "passive"))
      (node (ref "U1") (pin "28") (pinfunction "ADC5_/_SCL_/_PCINT13_/_PC5_28") (pintype "passive"))
    )
    (net (code "39") (name "/BUTTON_RESETn") (class "Default")
      (node (ref "D6") (pin "2") (pinfunction "Anode_2") (pintype "passive"))
      (node (ref "R20") (pin "1") (pinfunction "3_1") (pintype "passive"))
      (node (ref "R24") (pin "1") (pinfunction "3_1") (pintype "passive"))
      (node (ref "SW1") (pin "1") (pinfunction "1_1") (pintype "passive"))
      (node (ref "SW1") (pin "2") (pinfunction "2_2") (pintype "passive"))
    )
    (net (code "40") (name "/CON_USB_N") (class "Default")
      (node (ref "J7") (pin "2") (pinfunction "2_2") (pintype "passive"))
      (node (ref "R6") (pin "1") (pinfunction "3_1") (pintype "passive"))
      (node (ref "Z1") (pin "2") (pinfunction "2_2") (pintype "passive"))
    )
    (net (code "41") (name "/CON_USB_P") (class "Default")
      (node (ref "J7") (pin "3") (pinfunction "3_3") (pintype "passive"))
      (node (ref "R7") (pin "1") (pinfunction "3_1") (pintype "passive"))
      (node (ref "Z2") (pin "2") (pinfunction "2_2") (pintype "passive"))
    )
    (net (code "42") (name "/IO0") (class "Default")
      (node (ref "J3") (pin "1") (pinfunction "1_1") (pintype "passive"))
      (node (ref "R10") (pin "2") (pinfunction "4_2") (pintype "passive"))
      (node (ref "U1") (pin "2") (pinfunction "PCINT16_/_RXD_/_PD0_2") (pintype "passive"))
    )
    (net (code "43") (name "/IO1") (class "Default")
      (node (ref "J3") (pin "2") (pinfunction "2_2") (pintype "passive"))
      (node (ref "R11") (pin "2") (pinfunction "4_2") (pintype "passive"))
      (node (ref "U1") (pin "3") (pinfunction "PCINT17_/_TXD_/_PD1_3") (pintype "passive"))
    )
    (net (code "44") (name "/IO2") (class "Default")
      (node (ref "J3") (pin "3") (pinfunction "3_3") (pintype "passive"))
      (node (ref "U1") (pin "4") (pinfunction "PCINT18_/_INT0_/_PD2_4") (pintype "passive"))
    )
    (net (code "45") (name "/IO3") (class "Default")
      (node (ref "J3") (pin "4") (pinfunction "4_4") (pintype "passive"))
      (node (ref "U1") (pin "5") (pinfunction "PCINT19_/_OC2B_/_INT1_/_PD3_5") (pintype "passive"))
    )
    (net (code "46") (name "/IO4") (class "Default")
      (node (ref "J3") (pin "5") (pinfunction "5_5") (pintype "passive"))
      (node (ref "U1") (pin "6") (pinfunction "PCINT20_/_XCK_/_T0_/_PD4_6") (pintype "passive"))
    )
    (net (code "47") (name "/IO5") (class "Default")
      (node (ref "J3") (pin "6") (pinfunction "6_6") (pintype "passive"))
      (node (ref "U1") (pin "11") (pinfunction "PCINT21_/_OC0B_/_T1_/_PD5_11") (pintype "passive"))
    )
    (net (code "48") (name "/IO6") (class "Default")
      (node (ref "J3") (pin "7") (pinfunction "7_7") (pintype "passive"))
      (node (ref "U1") (pin "12") (pinfunction "PCINT22_/_OC0A_/_AIN0_/_PD6_12") (pintype "passive"))
    )
    (net (code "49") (name "/IO7") (class "Default")
      (node (ref "J3") (pin "8") (pinfunction "8_8") (pintype "passive"))
      (node (ref "U1") (pin "13") (pinfunction "PCINT23_/_AIN1_/_PD7_13") (pintype "passive"))
    )
    (net (code "50") (name "/IO8") (class "Default")
      (node (ref "J4") (pin "1") (pinfunction "1_1") (pintype "passive"))
      (node (ref "R22") (pin "2") (pinfunction "4_2") (pintype "passive"))
      (node (ref "U1") (pin "14") (pinfunction "(PCINT0/CLKO/ICP1)_PB0_14") (pintype "passive"))
    )
    (net (code "51") (name "/IO9") (class "Default")
      (node (ref "J4") (pin "2") (pinfunction "2_2") (pintype "passive"))
      (node (ref "U1") (pin "15") (pinfunction "OC1A_/_PCINT1_/_PB1_15") (pintype "passive"))
    )
    (net (code "52") (name "/MISO") (class "Default")
      (node (ref "J4") (pin "5") (pinfunction "5_5") (pintype "passive"))
      (node (ref "J5") (pin "1") (pinfunction "1_1") (pintype "passive"))
      (node (ref "U1") (pin "18") (pinfunction "MISO_/_PCINT4_/_PB4_18") (pintype "passive"))
    )
    (net (code "53") (name "/MOSI") (class "Default")
      (node (ref "J4") (pin "4") (pinfunction "4_4") (pintype "passive"))
      (node (ref "J5") (pin "4") (pinfunction "4_4") (pintype "passive"))
      (node (ref "U1") (pin "17") (pinfunction "MOSI_/_OC2A_/_PCINT3_/_PB3_17") (pintype "passive"))
    )
    (net (code "54") (name "/SCK") (class "Default")
      (node (ref "J4") (pin "6") (pinfunction "6_6") (pintype "passive"))
      (node (ref "J5") (pin "3") (pinfunction "3_3") (pintype "passive"))
      (node (ref "R13") (pin "2") (pinfunction "4_2") (pintype "passive"))
      (node (ref "U4") (pin "1") (pinfunction "1_1") (pintype "passive"))
      (node (ref "U4") (pin "2") (pinfunction "2_2") (pintype "passive"))
    )
    (net (code "55") (name "/SCK_R") (class "Default")
      (node (ref "R13") (pin "1") (pinfunction "3_1") (pintype "passive"))
      (node (ref "U1") (pin "19") (pinfunction "SCK_/_PCINT5_/_PB5_19") (pintype "passive"))
    )
    (net (code "56") (name "/SS") (class "Default")
      (node (ref "J4") (pin "3") (pinfunction "3_3") (pintype "passive"))
      (node (ref "U1") (pin "16") (pinfunction "SS_/_OC1B_/_PCINT2_/_PB2_16") (pintype "passive"))
    )
    (net (code "57") (name "/USB_N") (class "Default")
      (node (ref "R6") (pin "2") (pinfunction "4_2") (pintype "passive"))
      (node (ref "U2") (pin "30") (pinfunction "D-_30") (pintype "passive"))
    )
    (net (code "58") (name "/USB_P") (class "Default")
      (node (ref "R7") (pin "2") (pinfunction "4_2") (pintype "passive"))
      (node (ref "U2") (pin "29") (pinfunction "D+_29") (pintype "passive"))
    )
    (net (code "59") (name "/USER_BUTTON") (class "Default")
      (node (ref "R21") (pin "1") (pinfunction "3_1") (pintype "passive"))
      (node (ref "R25") (pin "1") (pinfunction "3_1") (pintype "passive"))
      (node (ref "SW2") (pin "1") (pinfunction "1_1") (pintype "passive"))
      (node (ref "SW2") (pin "2") (pinfunction "2_2") (pintype "passive"))
    )
    (net (code "60") (name "/USER_BUTTON_BUF") (class "Default")
      (node (ref "C33") (pin "2") (pinfunction "2_2") (pintype "passive"))
      (node (ref "R25") (pin "2") (pinfunction "4_2") (pintype "passive"))
      (node (ref "U7") (pin "1") (pinfunction "1_1") (pintype "passive"))
      (node (ref "U7") (pin "2") (pinfunction "2_2") (pintype "passive"))
    )
    (net (code "61") (name "GND") (class "Default")
      (node (ref "C1") (pin "2") (pinfunction "2_2") (pintype "passive"))
      (node (ref "C10") (pin "1") (pinfunction "1_1") (pintype "passive"))
      (node (ref "C12") (pin "2") (pinfunction "2_2") (pintype "passive"))
      (node (ref "C13") (pin "2") (pinfunction "2_2") (pintype "passive"))
      (node (ref "C14") (pin "1") (pinfunction "1_1") (pintype "passive"))
      (node (ref "C15") (pin "1") (pinfunction "1_1") (pintype "passive"))
      (node (ref "C16") (pin "1") (pinfunction "1_1") (pintype "passive"))
      (node (ref "C17") (pin "1") (pinfunction "1_1") (pintype "passive"))
      (node (ref "C19") (pin "1") (pinfunction "1_1") (pintype "passive"))
      (node (ref "C2") (pin "2") (pinfunction "2_2") (pintype "passive"))
      (node (ref "C20") (pin "1") (pinfunction "1_1") (pintype "passive"))
      (node (ref "C21") (pin "1") (pinfunction "1_1") (pintype "passive"))
      (node (ref "C22") (pin "1") (pinfunction "1_1") (pintype "passive"))
      (node (ref "C23") (pin "1") (pinfunction "1_1") (pintype "passive"))
      (node (ref "C24") (pin "1") (pinfunction "1_1") (pintype "passive"))
      (node (ref "C25") (pin "1") (pinfunction "1_1") (pintype "passive"))
      (node (ref "C26") (pin "2") (pinfunction "2_2") (pintype "passive"))
      (node (ref "C27") (pin "1") (pinfunction "1_1") (pintype "passive"))
      (node (ref "C28") (pin "1") (pinfunction "1_1") (pintype "passive"))
      (node (ref "C29") (pin "1") (pinfunction "1_1") (pintype "passive"))
      (node (ref "C3") (pin "1") (pinfunction "1_1") (pintype "passive"))
      (node (ref "C30") (pin "1") (pinfunction "1_1") (pintype "passive"))
      (node (ref "C31") (pin "1") (pinfunction "1_1") (pintype "passive"))
      (node (ref "C32") (pin "1") (pinfunction "1_1") (pintype "passive"))
      (node (ref "C33") (pin "1") (pinfunction "1_1") (pintype "passive"))
      (node (ref "C34") (pin "1") (pinfunction "1_1") (pintype "passive"))
      (node (ref "C4") (pin "1") (pinfunction "1_1") (pintype "passive"))
      (node (ref "C5") (pin "1") (pinfunction "1_1") (pintype "passive"))
      (node (ref "C6") (pin "1") (pinfunction "1_1") (pintype "passive"))
      (node (ref "C7") (pin "1") (pinfunction "1_1") (pintype "passive"))
      (node (ref "C8") (pin "1") (pinfunction "1_1") (pintype "passive"))
      (node (ref "C9") (pin "1") (pinfunction "1_1") (pintype "passive"))
      (node (ref "D1") (pin "1") (pinfunction "Cathode_1") (pintype "passive"))
      (node (ref "J1") (pin "6") (pinfunction "6_6") (pintype "passive"))
      (node (ref "J1") (pin "7") (pinfunction "7_7") (pintype "passive"))
      (node (ref "J4") (pin "7") (pinfunction "7_7") (pintype "passive"))
      (node (ref "J5") (pin "6") (pinfunction "6_6") (pintype "passive"))
      (node (ref "J6") (pin "6") (pinfunction "6_6") (pintype "passive"))
      (node (ref "J7") (pin "10") (pinfunction "10_10") (pintype "passive"))
      (node (ref "J7") (pin "11") (pinfunction "11_11") (pintype "passive"))
      (node (ref "J7") (pin "5") (pinfunction "5_5") (pintype "passive"))
      (node (ref "J7") (pin "6") (pinfunction "6_6") (pintype "passive"))
      (node (ref "J7") (pin "7") (pinfunction "7_7") (pintype "passive"))
      (node (ref "J7") (pin "8") (pinfunction "8_8") (pintype "passive"))
      (node (ref "J7") (pin "9") (pinfunction "9_9") (pintype "passive"))
      (node (ref "J9") (pin "1") (pinfunction "1_1") (pintype "passive"))
      (node (ref "MH1") (pin "1") (pinfunction "1_1") (pintype "passive"))
      (node (ref "MH2") (pin "1") (pinfunction "1_1") (pintype "passive"))
      (node (ref "MH3") (pin "1") (pinfunction "1_1") (pintype "passive"))
      (node (ref "R12") (pin "1") (pinfunction "3_1") (pintype "passive"))
      (node (ref "R8") (pin "2") (pinfunction "4_2") (pintype "passive"))
      (node (ref "SW1") (pin "3") (pinfunction "3_3") (pintype "passive"))
      (node (ref "SW1") (pin "4") (pinfunction "4_4") (pintype "passive"))
      (node (ref "SW2") (pin "3") (pinfunction "3_3") (pintype "passive"))
      (node (ref "SW2") (pin "4") (pinfunction "4_4") (pintype "passive"))
      (node (ref "U1") (pin "22") (pinfunction "GND_2_22") (pintype "passive"))
      (node (ref "U1") (pin "8") (pinfunction "GND_1_8") (pintype "passive"))
      (node (ref "U2") (pin "28") (pinfunction "UGND_28") (pintype "passive"))
      (node (ref "U2") (pin "3") (pinfunction "GND_3") (pintype "passive"))
      (node (ref "U3") (pin "3") (pinfunction "GND_3") (pintype "passive"))
      (node (ref "U3") (pin "6") (pinfunction "EPAD_6") (pintype "passive"))
      (node (ref "U4") (pin "3") (pinfunction "3_3") (pintype "passive"))
      (node (ref "U5") (pin "3") (pinfunction "3_3") (pintype "passive"))
      (node (ref "U6") (pin "3") (pinfunction "3_3") (pintype "passive"))
      (node (ref "U7") (pin "3") (pinfunction "3_3") (pintype "passive"))
      (node (ref "Z1") (pin "1") (pinfunction "1_1") (pintype "passive"))
      (node (ref "Z2") (pin "1") (pinfunction "1_1") (pintype "passive"))
    )
    (net (code "62") (name "Net-(C11-Pad2)") (class "Default")
      (node (ref "C11") (pin "2") (pinfunction "2_2") (pintype "passive"))
      (node (ref "JP1") (pin "1") (pinfunction "1_1") (pintype "passive"))
    )
    (net (code "63") (name "Net-(D1-Anode)") (class "Default")
      (node (ref "D1") (pin "2") (pinfunction "Anode_2") (pintype "passive"))
      (node (ref "R17") (pin "2") (pinfunction "4_2") (pintype "passive"))
    )
    (net (code "64") (name "Net-(D2-Anode)") (class "Default")
      (node (ref "D2") (pin "2") (pinfunction "Anode_2") (pintype "passive"))
      (node (ref "R15") (pin "2") (pinfunction "4_2") (pintype "passive"))
    )
    (net (code "65") (name "Net-(D2-Cathode)") (class "Default")
      (node (ref "D2") (pin "1") (pinfunction "Cathode_1") (pintype "passive"))
      (node (ref "U4") (pin "4") (pinfunction "4_4") (pintype "passive"))
    )
    (net (code "66") (name "Net-(D3-Anode)") (class "Default")
      (node (ref "D3") (pin "2") (pinfunction "Anode_2") (pintype "passive"))
      (node (ref "R2") (pin "2") (pinfunction "4_2") (pintype "passive"))
    )
    (net (code "67") (name "Net-(D4-Anode)") (class "Default")
      (node (ref "D4") (pin "2") (pinfunction "Anode_2") (pintype "passive"))
      (node (ref "R3") (pin "2") (pinfunction "4_2") (pintype "passive"))
    )
    (net (code "68") (name "Net-(D5-Anode)") (class "Default")
      (node (ref "D5") (pin "2") (pinfunction "Anode_2") (pintype "passive"))
      (node (ref "R19") (pin "1") (pinfunction "3_1") (pintype "passive"))
      (node (ref "R23") (pin "1") (pinfunction "3_1") (pintype "passive"))
    )
    (net (code "69") (name "Net-(R8-3)") (class "Default")
      (node (ref "J7") (pin "4") (pinfunction "4_4") (pintype "passive"))
      (node (ref "R8") (pin "1") (pinfunction "3_1") (pintype "passive"))
    )
    (net (code "70") (name "Net-(R12-4)") (class "Default")
      (node (ref "JP1") (pin "3") (pinfunction "3_3") (pintype "passive"))
      (node (ref "R12") (pin "2") (pinfunction "4_2") (pintype "passive"))
    )
    (net (code "71") (name "Net-(R22-3)") (class "Default")
      (node (ref "R22") (pin "1") (pinfunction "3_1") (pintype "passive"))
      (node (ref "U7") (pin "4") (pinfunction "4_4") (pintype "passive"))
    )
    (net (code "72") (name "unconnected-(J1-Pad1)") (class "Default")
      (node (ref "J1") (pin "1") (pinfunction "1_1") (pintype "passive+no_connect"))
    )
    (net (code "73") (name "unconnected-(J1-Pad8)") (class "Default")
      (node (ref "J1") (pin "8") (pinfunction "8_8") (pintype "passive+no_connect"))
    )
    (net (code "74") (name "unconnected-(MH4-Pad1)") (class "Default")
      (node (ref "MH4") (pin "1") (pinfunction "1_1") (pintype "passive+no_connect"))
    )
    (net (code "75") (name "unconnected-(U2-AIN0_{slash}_INT1{slash}_PD1-Pad7)") (class "Default")
      (node (ref "U2") (pin "7") (pinfunction "AIN0_/_INT1/_PD1_7") (pintype "passive+no_connect"))
    )
    (net (code "76") (name "unconnected-(U2-AIN2_{slash}PCINT11_{slash}_PC2-Pad5)") (class "Default")
      (node (ref "U2") (pin "5") (pinfunction "AIN2_/PCINT11_/_PC2_5") (pintype "passive+no_connect"))
    )
    (net (code "77") (name "unconnected-(U2-CLKO_{slash}_ICP1_{slash}_INT4_{slash}_PC7-Pad22)") (class "Default")
      (node (ref "U2") (pin "22") (pinfunction "CLKO_/_ICP1_/_INT4_/_PC7_22") (pintype "passive+no_connect"))
    )
    (net (code "78") (name "unconnected-(U2-OC.0B_{slash}_INT0_{slash}_PD0-Pad6)") (class "Default")
      (node (ref "U2") (pin "6") (pinfunction "OC.0B_/_INT0_/_PD0_6") (pintype "passive+no_connect"))
    )
    (net (code "79") (name "unconnected-(U2-OC.1A_{slash}_PCINT8_{slash}_PC6-Pad23)") (class "Default")
      (node (ref "U2") (pin "23") (pinfunction "OC.1A_/_PCINT8_/_PC6_23") (pintype "passive+no_connect"))
    )
    (net (code "80") (name "unconnected-(U2-OC.1B_{slash}_PCINT9_{slash}_PC5-Pad25)") (class "Default")
      (node (ref "U2") (pin "25") (pinfunction "OC.1B_/_PCINT9_/_PC5_25") (pintype "passive+no_connect"))
    )
    (net (code "81") (name "unconnected-(U2-PCINT10_{slash}_PC4-Pad26)") (class "Default")
      (node (ref "U2") (pin "26") (pinfunction "PCINT10_/_PC4_26") (pintype "passive+no_connect"))
    )
    (net (code "82") (name "unconnected-(U2-~{RTS}_{slash}_AIN5_{slash}_INT6_{slash}_PD6-Pad12)") (class "Default")
      (node (ref "U2") (pin "12") (pinfunction "~{RTS}_/_AIN5_/_INT6_/_PD6_12") (pintype "passive"))
    )
    (net (code "83") (name "unconnected-(U2-~{SS}_{slash}_PCINT0_{slash}_PB0-Pad14)") (class "Default")
      (node (ref "U2") (pin "14") (pinfunction "~{SS}_/_PCINT0_/_PB0_14") (pintype "passive+no_connect"))
    )
  )
)
